# RelayA.net
KiCad netlist of a schematic drawn in Altium Designer
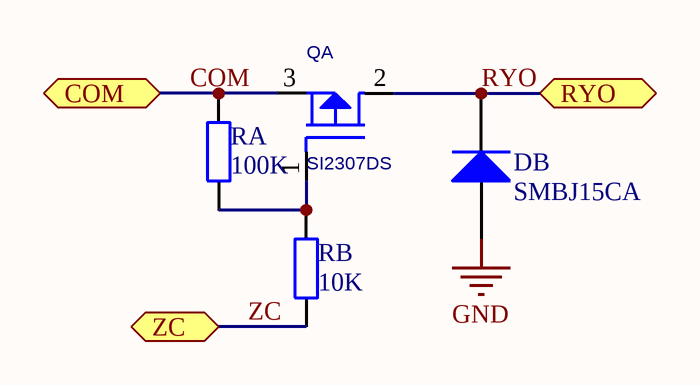
[diagram p0: RelayA.SchDoc]

(export (version "E")
  (design (tool "Eeschema 10.0.6"))
  (components
    (comp (ref "DB")
      (value "SMBJ15CA")
      (footprint "SO-0.4A")
      (description "1 Amp General Purpose Rectifier")
      (fields (field (name "PUBLISHER") "Altium Limited"))
      (libsource (lib "Miscellaneous Devices") (part "Diode 1N4001"))
    )
    (comp (ref "QA") (value "SI2307DS") (footprint "SOT-23") (libsource (lib "*") (part "MOSFET P_1")))
    (comp (ref "RA")
      (value "100K")
      (footprint "R0603")
      (description "Resistor")
      (fields (field (name "PUBLISHER") "Altium Limited"))
      (libsource (lib "Miscellaneous Devices") (part "Res2"))
    )
    (comp (ref "RB")
      (value "10K")
      (footprint "R0603")
      (description "Resistor")
      (fields (field (name "PUBLISHER") "Altium Limited"))
      (libsource (lib "Miscellaneous Devices") (part "Res2"))
    )
  )
  (nets
    (net (code "1") (name "/COM") (class "Default")
      (node (ref "QA") (pin "3") (pinfunction "SOURCE_3") (pintype "passive"))
      (node (ref "RA") (pin "2") (pinfunction "2_2") (pintype "passive"))
    )
    (net (code "2") (name "/RYO") (class "Default")
      (node (ref "DB") (pin "K") (pinfunction "K_K") (pintype "passive"))
      (node (ref "QA") (pin "2") (pinfunction "DRAIN_2") (pintype "passive"))
    )
    (net (code "3") (name "/ZC") (class "Default")
      (node (ref "RB") (pin "1") (pinfunction "1_1") (pintype "passive"))
    )
    (net (code "4") (name "GND") (class "Default")
      (node (ref "DB") (pin "A") (pinfunction "A_A") (pintype "passive"))
    )
    (net (code "5") (name "Net-(QA-GATE)") (class "Default")
      (node (ref "QA") (pin "1") (pinfunction "GATE_1") (pintype "passive"))
      (node (ref "RA") (pin "1") (pinfunction "1_1") (pintype "passive"))
      (node (ref "RB") (pin "2") (pinfunction "2_2") (pintype "passive"))
    )
  )
)
